# UWB-Anchor_Sch.net
KiCad netlist of a schematic drawn in Altium Designer
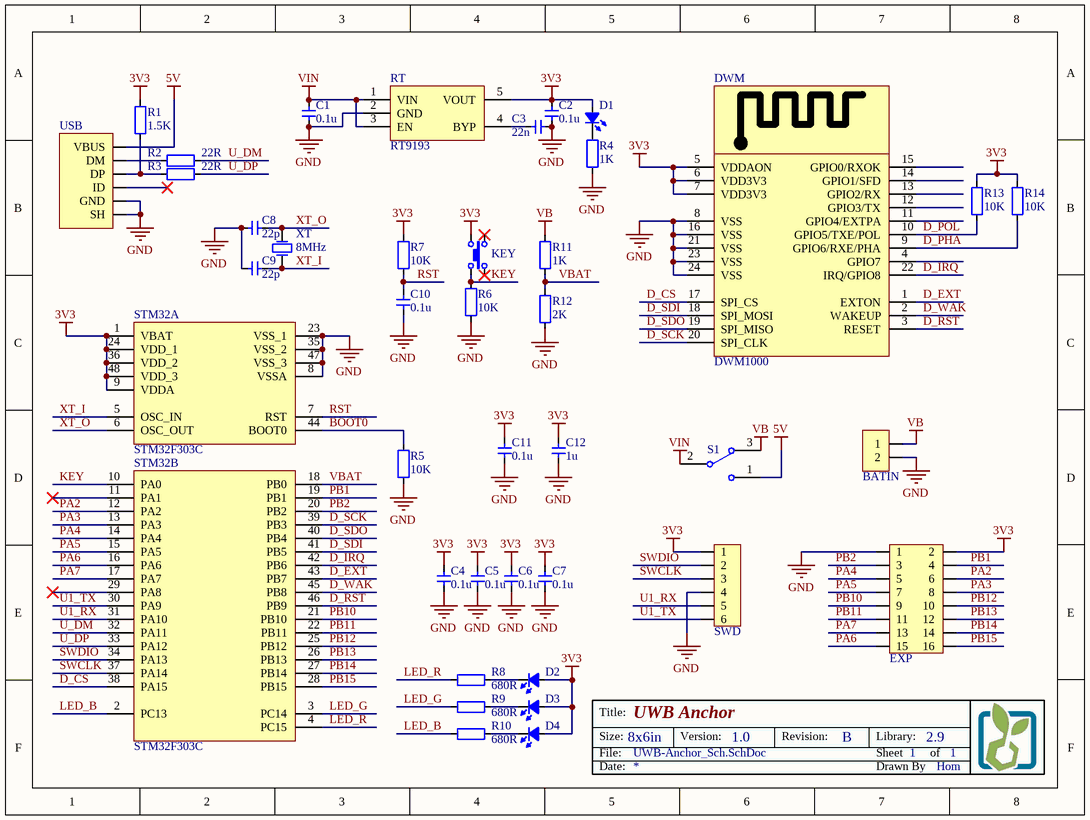
[diagram p0: UWB-Anchor_Sch.SchDoc]

(export (version "E")
  (design (tool "Eeschema 10.0.6"))
  (components
    (comp (ref "BATIN")
      (value "MX1.25_2P")
      (footprint "PCB_Connector:MX1.25_S90_2P")
      (description "MX")
      (libsource (lib "SCH_Connector") (part "MX1.25_2P"))
    )
    (comp (ref "C1")
      (value "0.1u")
      (footprint "PCB_PassiveCap:CAP_0603")
      (description "Capacitor")
      (fields (field (name "Comment") "Cap_0603"))
      (libsource (lib "SCH_Passive") (part "Cap_0603"))
    )
    (comp (ref "C2")
      (value "0.1u")
      (footprint "PCB_PassiveCap:CAP_0603")
      (description "Capacitor")
      (fields (field (name "Comment") "Cap_0603"))
      (libsource (lib "SCH_Passive") (part "Cap_0603"))
    )
    (comp (ref "C3")
      (value "22n")
      (footprint "PCB_PassiveCap:CAP_0603")
      (description "Capacitor")
      (fields (field (name "Comment") "Cap_0603"))
      (libsource (lib "SCH_Passive") (part "Cap_0603"))
    )
    (comp (ref "C4")
      (value "0.1u")
      (footprint "PCB_PassiveCap:CAP_0603")
      (description "Capacitor")
      (fields (field (name "Comment") "Cap_0603"))
      (libsource (lib "SCH_Passive") (part "Cap_0603"))
    )
    (comp (ref "C5")
      (value "0.1u")
      (footprint "PCB_PassiveCap:CAP_0603")
      (description "Capacitor")
      (fields (field (name "Comment") "Cap_0603"))
      (libsource (lib "SCH_Passive") (part "Cap_0603"))
    )
    (comp (ref "C6")
      (value "0.1u")
      (footprint "PCB_PassiveCap:CAP_0603")
      (description "Capacitor")
      (fields (field (name "Comment") "Cap_0603"))
      (libsource (lib "SCH_Passive") (part "Cap_0603"))
    )
    (comp (ref "C7")
      (value "0.1u")
      (footprint "PCB_PassiveCap:CAP_0603")
      (description "Capacitor")
      (fields (field (name "Comment") "Cap_0603"))
      (libsource (lib "SCH_Passive") (part "Cap_0603"))
    )
    (comp (ref "C8")
      (value "22p")
      (footprint "PCB_PassiveCap:CAP_0603")
      (description "Capacitor")
      (fields (field (name "Comment") "Cap_0603"))
      (libsource (lib "SCH_Passive") (part "Cap_0603"))
    )
    (comp (ref "C9")
      (value "22p")
      (footprint "PCB_PassiveCap:CAP_0603")
      (description "Capacitor")
      (fields (field (name "Comment") "Cap_0603"))
      (libsource (lib "SCH_Passive") (part "Cap_0603"))
    )
    (comp (ref "C10")
      (value "0.1u")
      (footprint "PCB_PassiveCap:CAP_0603")
      (description "Capacitor")
      (fields (field (name "Comment") "Cap_0603"))
      (libsource (lib "SCH_Passive") (part "Cap_0603"))
    )
    (comp (ref "C11")
      (value "0.1u")
      (footprint "PCB_PassiveCap:CAP_0603")
      (description "Capacitor")
      (fields (field (name "Comment") "Cap_0603"))
      (libsource (lib "SCH_Passive") (part "Cap_0603"))
    )
    (comp (ref "C12")
      (value "1u")
      (footprint "PCB_PassiveCap:CAP_0603")
      (description "Capacitor")
      (fields (field (name "Comment") "Cap_0603"))
      (libsource (lib "SCH_Passive") (part "Cap_0603"))
    )
    (comp (ref "D1")
      (value "LED_0603")
      (footprint "PCB_ActiveLED:LED_0603_YELLOW")
      (description "LED")
      (libsource (lib "SCH_Active") (part "LED_0603"))
    )
    (comp (ref "D2")
      (value "LED_0603")
      (footprint "PCB_ActiveLED:LED_0603_RED")
      (description "LED")
      (libsource (lib "SCH_Active") (part "LED_0603"))
    )
    (comp (ref "D3")
      (value "LED_0603")
      (footprint "PCB_ActiveLED:LED_0603_GREEN")
      (description "LED")
      (libsource (lib "SCH_Active") (part "LED_0603"))
    )
    (comp (ref "D4")
      (value "LED_0603")
      (footprint "PCB_ActiveLED:LED_0603_BLUE")
      (description "LED")
      (libsource (lib "SCH_Active") (part "LED_0603"))
    )
    (comp (ref "DWM")
      (value "DWM1000")
      (footprint "PCB_Module:DWM1000")
      (description "Module")
      (fields (field (name "MANUFACTURER") "Decawave Limited"))
      (libsource (lib "SCH_Module") (part "DWM1000"))
    )
    (comp (ref "EXP")
      (value "HDR2x8_2.54")
      (footprint "PCB_ConnectorHDR:HDR2X8_2.54_180")
      (description "Header")
      (libsource (lib "SCH_ConnectorHDR") (part "HDR2x8_2.54"))
    )
    (comp (ref "KEY")
      (value "ButtonTACT")
      (footprint "PCB_Switch:ButtonTACT_3.5*3.55_90")
      (description "Button")
      (libsource (lib "SCH_Switch") (part "ButtonTACT"))
    )
    (comp (ref "R1")
      (value "1.5K")
      (footprint "PCB_PassiveRes:RES_0603")
      (description "Resistor")
      (fields (field (name "Comment") "Res_0603"))
      (libsource (lib "") (part "Res_0603_1"))
    )
    (comp (ref "R2")
      (value "22R")
      (footprint "PCB_PassiveRes:RES_0603")
      (description "Resistor")
      (fields (field (name "Comment") "Res_0603"))
      (libsource (lib "") (part "Res_0603_3"))
    )
    (comp (ref "R3")
      (value "22R")
      (footprint "PCB_PassiveRes:RES_0603")
      (description "Resistor")
      (fields (field (name "Comment") "Res_0603"))
      (libsource (lib "") (part "Res_0603_3"))
    )
    (comp (ref "R4")
      (value "1K")
      (footprint "PCB_PassiveRes:RES_0603")
      (description "Resistor")
      (fields (field (name "Comment") "Res_0603"))
      (libsource (lib "") (part "Res_0603_2"))
    )
    (comp (ref "R5")
      (value "10K")
      (footprint "PCB_PassiveRes:RES_0603")
      (description "Resistor")
      (fields (field (name "Comment") "Res_0603"))
      (libsource (lib "") (part "Res_0603_2"))
    )
    (comp (ref "R6")
      (value "10K")
      (footprint "PCB_PassiveRes:RES_0603")
      (description "Resistor")
      (fields (field (name "Comment") "Res_0603"))
      (libsource (lib "") (part "Res_0603_2"))
    )
    (comp (ref "R7")
      (value "10K")
      (footprint "PCB_PassiveRes:RES_0603")
      (description "Resistor")
      (fields (field (name "Comment") "Res_0603"))
      (libsource (lib "") (part "Res_0603_2"))
    )
    (comp (ref "R8")
      (value "680R")
      (footprint "PCB_PassiveRes:RES_0603")
      (description "Resistor")
      (fields (field (name "Comment") "Res_0603"))
      (libsource (lib "SCH_Passive") (part "Res_0603"))
    )
    (comp (ref "R9")
      (value "680R")
      (footprint "PCB_PassiveRes:RES_0603")
      (description "Resistor")
      (fields (field (name "Comment") "Res_0603"))
      (libsource (lib "SCH_Passive") (part "Res_0603"))
    )
    (comp (ref "R10")
      (value "680R")
      (footprint "PCB_PassiveRes:RES_0603")
      (description "Resistor")
      (fields (field (name "Comment") "Res_0603"))
      (libsource (lib "SCH_Passive") (part "Res_0603"))
    )
    (comp (ref "R11")
      (value "1K")
      (footprint "PCB_PassiveRes:RES_0603")
      (description "Resistor")
      (fields (field (name "Comment") "Res_0603"))
      (libsource (lib "") (part "Res_0603_1"))
    )
    (comp (ref "R12")
      (value "2K")
      (footprint "PCB_PassiveRes:RES_0603")
      (description "Resistor")
      (fields (field (name "Comment") "Res_0603"))
      (libsource (lib "") (part "Res_0603_1"))
    )
    (comp (ref "R13")
      (value "10K")
      (footprint "PCB_PassiveRes:RES_0603")
      (description "Resistor")
      (fields (field (name "Comment") "Res_0603"))
      (libsource (lib "") (part "Res_0603_2"))
    )
    (comp (ref "R14")
      (value "10K")
      (footprint "PCB_PassiveRes:RES_0603")
      (description "Resistor")
      (fields (field (name "Comment") "Res_0603"))
      (libsource (lib "") (part "Res_0603_2"))
    )
    (comp (ref "RT")
      (value "RT9193")
      (footprint "PCB_IntegratedCircuit:SOT23-5")
      (description "Power")
      (libsource (lib "SCH_IntegratedCircuit") (part "RT9193"))
    )
    (comp (ref "S1")
      (value "SwitchSPDT_2.8x6.6_90")
      (footprint "PCB_Switch:SwitchSPDT_2.8X6.6_90")
      (description "Switch")
      (libsource (lib "SCH_Switch") (part "SwitchSPDT_2.8x6.6_90"))
    )
    (comp (ref "STM32")
      (value "STM32F303C")
      (footprint "PCB_IntegratedCircuit:LQFP_P0.5_48")
      (description "MCU")
      (libsource (lib "SCH_IntegratedCircuit") (part "STM32F103C"))
    )
    (comp (ref "SWD")
      (value "HDR1x6_1.27")
      (footprint "PCB_ConnectorHDR:HDR1X6_1.27_180HFD")
      (description "Header")
      (libsource (lib "SCH_ConnectorHDR") (part "HDR1x6_1.27"))
    )
    (comp (ref "USB")
      (value "USB_Micro")
      (footprint "PCB_USB:USB_Micro-AB")
      (description "USB")
      (libsource (lib "SCH_USB") (part "USB_Micro"))
    )
    (comp (ref "XT")
      (value "8MHz")
      (footprint "PCB_Oscillator:XT_5032_2")
      (description "Crystal Oscillator")
      (fields (field (name "Comment") "XTAL_5032_2P"))
      (libsource (lib "SCH_Oscillator") (part "XTAL_5032_2P"))
    )
  )
  (nets
    (net (code "1") (name "/BOOT0") (class "Default")
      (node (ref "R5") (pin "2") (pinfunction "2_2") (pintype "passive"))
      (node (ref "STM32") (pin "44") (pinfunction "BOOT0_44") (pintype "passive"))
    )
    (net (code "2") (name "/D_CS") (class "Default")
      (node (ref "DWM") (pin "17") (pinfunction "SPI_CS_17") (pintype "passive"))
      (node (ref "STM32") (pin "38") (pinfunction "PA15_38") (pintype "passive"))
    )
    (net (code "3") (name "/D_EXT") (class "Default")
      (node (ref "DWM") (pin "1") (pinfunction "EXTON_1") (pintype "passive"))
      (node (ref "STM32") (pin "43") (pinfunction "PB7_43") (pintype "passive"))
    )
    (net (code "4") (name "/D_IRQ") (class "Default")
      (node (ref "DWM") (pin "22") (pinfunction "IRQ/GPIO8_22") (pintype "passive"))
      (node (ref "STM32") (pin "42") (pinfunction "PB6_42") (pintype "passive"))
    )
    (net (code "5") (name "/D_PHA") (class "Default")
      (node (ref "DWM") (pin "9") (pinfunction "GPIO6/RXE/PHA_9") (pintype "passive"))
      (node (ref "R14") (pin "1") (pinfunction "1_1") (pintype "passive"))
    )
    (net (code "6") (name "/D_POL") (class "Default")
      (node (ref "DWM") (pin "10") (pinfunction "GPIO5/TXE/POL_10") (pintype "passive"))
      (node (ref "R13") (pin "1") (pinfunction "1_1") (pintype "passive"))
    )
    (net (code "7") (name "/D_RST") (class "Default")
      (node (ref "DWM") (pin "3") (pinfunction "RESET_3") (pintype "passive"))
      (node (ref "STM32") (pin "46") (pinfunction "PB9_46") (pintype "passive"))
    )
    (net (code "8") (name "/D_SCK") (class "Default")
      (node (ref "DWM") (pin "20") (pinfunction "SPI_CLK_20") (pintype "passive"))
      (node (ref "STM32") (pin "39") (pinfunction "PB3_39") (pintype "passive"))
    )
    (net (code "9") (name "/D_SDI") (class "Default")
      (node (ref "DWM") (pin "18") (pinfunction "SPI_MOSI_18") (pintype "passive"))
      (node (ref "STM32") (pin "41") (pinfunction "PB5_41") (pintype "passive"))
    )
    (net (code "10") (name "/D_SDO") (class "Default")
      (node (ref "DWM") (pin "19") (pinfunction "SPI_MISO_19") (pintype "passive"))
      (node (ref "STM32") (pin "40") (pinfunction "PB4_40") (pintype "passive"))
    )
    (net (code "11") (name "/D_WAK") (class "Default")
      (node (ref "DWM") (pin "2") (pinfunction "WAKEUP_2") (pintype "passive"))
      (node (ref "STM32") (pin "45") (pinfunction "PB8_45") (pintype "passive"))
    )
    (net (code "12") (name "/KEY") (class "Default")
      (node (ref "KEY") (pin "1") (pinfunction "1_1") (pintype "passive"))
      (node (ref "R6") (pin "2") (pinfunction "2_2") (pintype "passive"))
      (node (ref "STM32") (pin "10") (pinfunction "PA0_10") (pintype "passive"))
    )
    (net (code "13") (name "/LED_B") (class "Default")
      (node (ref "R10") (pin "2") (pinfunction "2_2") (pintype "passive"))
      (node (ref "STM32") (pin "2") (pinfunction "PC13_2") (pintype "passive"))
    )
    (net (code "14") (name "/LED_G") (class "Default")
      (node (ref "R9") (pin "2") (pinfunction "2_2") (pintype "passive"))
      (node (ref "STM32") (pin "3") (pinfunction "PC14_3") (pintype "passive"))
    )
    (net (code "15") (name "/LED_R") (class "Default")
      (node (ref "R8") (pin "2") (pinfunction "2_2") (pintype "passive"))
      (node (ref "STM32") (pin "4") (pinfunction "PC15_4") (pintype "passive"))
    )
    (net (code "16") (name "/PA2") (class "Default")
      (node (ref "EXP") (pin "6") (pinfunction "6_6") (pintype "passive"))
      (node (ref "STM32") (pin "12") (pinfunction "PA2_12") (pintype "passive"))
    )
    (net (code "17") (name "/PA3") (class "Default")
      (node (ref "EXP") (pin "8") (pinfunction "8_8") (pintype "passive"))
      (node (ref "STM32") (pin "13") (pinfunction "PA3_13") (pintype "passive"))
    )
    (net (code "18") (name "/PA4") (class "Default")
      (node (ref "EXP") (pin "5") (pinfunction "5_5") (pintype "passive"))
      (node (ref "STM32") (pin "14") (pinfunction "PA4_14") (pintype "passive"))
    )
    (net (code "19") (name "/PA5") (class "Default")
      (node (ref "EXP") (pin "7") (pinfunction "7_7") (pintype "passive"))
      (node (ref "STM32") (pin "15") (pinfunction "PA5_15") (pintype "passive"))
    )
    (net (code "20") (name "/PA6") (class "Default")
      (node (ref "EXP") (pin "15") (pinfunction "15_15") (pintype "passive"))
      (node (ref "STM32") (pin "16") (pinfunction "PA6_16") (pintype "passive"))
    )
    (net (code "21") (name "/PA7") (class "Default")
      (node (ref "EXP") (pin "13") (pinfunction "13_13") (pintype "passive"))
      (node (ref "STM32") (pin "17") (pinfunction "PA7_17") (pintype "passive"))
    )
    (net (code "22") (name "/PB1") (class "Default")
      (node (ref "EXP") (pin "4") (pinfunction "4_4") (pintype "passive"))
      (node (ref "STM32") (pin "19") (pinfunction "PB1_19") (pintype "passive"))
    )
    (net (code "23") (name "/PB2") (class "Default")
      (node (ref "EXP") (pin "3") (pinfunction "3_3") (pintype "passive"))
      (node (ref "STM32") (pin "20") (pinfunction "PB2_20") (pintype "passive"))
    )
    (net (code "24") (name "/PB10") (class "Default")
      (node (ref "EXP") (pin "9") (pinfunction "9_9") (pintype "passive"))
      (node (ref "STM32") (pin "21") (pinfunction "PB10_21") (pintype "passive"))
    )
    (net (code "25") (name "/PB11") (class "Default")
      (node (ref "EXP") (pin "11") (pinfunction "11_11") (pintype "passive"))
      (node (ref "STM32") (pin "22") (pinfunction "PB11_22") (pintype "passive"))
    )
    (net (code "26") (name "/PB12") (class "Default")
      (node (ref "EXP") (pin "10") (pinfunction "10_10") (pintype "passive"))
      (node (ref "STM32") (pin "25") (pinfunction "PB12_25") (pintype "passive"))
    )
    (net (code "27") (name "/PB13") (class "Default")
      (node (ref "EXP") (pin "12") (pinfunction "12_12") (pintype "passive"))
      (node (ref "STM32") (pin "26") (pinfunction "PB13_26") (pintype "passive"))
    )
    (net (code "28") (name "/PB14") (class "Default")
      (node (ref "EXP") (pin "14") (pinfunction "14_14") (pintype "passive"))
      (node (ref "STM32") (pin "27") (pinfunction "PB14_27") (pintype "passive"))
    )
    (net (code "29") (name "/PB15") (class "Default")
      (node (ref "EXP") (pin "16") (pinfunction "16_16") (pintype "passive"))
      (node (ref "STM32") (pin "28") (pinfunction "PB15_28") (pintype "passive"))
    )
    (net (code "30") (name "/RST") (class "Default")
      (node (ref "C10") (pin "2") (pinfunction "2_2") (pintype "passive"))
      (node (ref "R7") (pin "1") (pinfunction "1_1") (pintype "passive"))
      (node (ref "STM32") (pin "7") (pinfunction "RST_7") (pintype "passive"))
    )
    (net (code "31") (name "/SWCLK") (class "Default")
      (node (ref "STM32") (pin "37") (pinfunction "PA14_37") (pintype "passive"))
      (node (ref "SWD") (pin "3") (pinfunction "3_3") (pintype "passive"))
    )
    (net (code "32") (name "/SWDIO") (class "Default")
      (node (ref "STM32") (pin "34") (pinfunction "PA13_34") (pintype "passive"))
      (node (ref "SWD") (pin "2") (pinfunction "2_2") (pintype "passive"))
    )
    (net (code "33") (name "/U1_RX") (class "Default")
      (node (ref "STM32") (pin "31") (pinfunction "PA10_31") (pintype "passive"))
      (node (ref "SWD") (pin "5") (pinfunction "5_5") (pintype "passive"))
    )
    (net (code "34") (name "/U1_TX") (class "Default")
      (node (ref "STM32") (pin "30") (pinfunction "PA9_30") (pintype "passive"))
      (node (ref "SWD") (pin "6") (pinfunction "6_6") (pintype "passive"))
    )
    (net (code "35") (name "/U_DM") (class "Default")
      (node (ref "R2") (pin "2") (pinfunction "2_2") (pintype "passive"))
      (node (ref "STM32") (pin "32") (pinfunction "PA11_32") (pintype "passive"))
    )
    (net (code "36") (name "/U_DP") (class "Default")
      (node (ref "R3") (pin "2") (pinfunction "2_2") (pintype "passive"))
      (node (ref "STM32") (pin "33") (pinfunction "PA12_33") (pintype "passive"))
    )
    (net (code "37") (name "/VBAT") (class "Default")
      (node (ref "R11") (pin "2") (pinfunction "2_2") (pintype "passive"))
      (node (ref "R12") (pin "1") (pinfunction "1_1") (pintype "passive"))
      (node (ref "STM32") (pin "18") (pinfunction "PB0_18") (pintype "passive"))
    )
    (net (code "38") (name "/XT_I") (class "Default")
      (node (ref "C9") (pin "1") (pinfunction "1_1") (pintype "passive"))
      (node (ref "STM32") (pin "5") (pinfunction "OSC_IN_5") (pintype "passive"))
      (node (ref "XT") (pin "1") (pinfunction "OSC1_1") (pintype "passive"))
    )
    (net (code "39") (name "/XT_O") (class "Default")
      (node (ref "C8") (pin "1") (pinfunction "1_1") (pintype "passive"))
      (node (ref "STM32") (pin "6") (pinfunction "OSC_OUT_6") (pintype "passive"))
      (node (ref "XT") (pin "2") (pinfunction "OSC2_2") (pintype "passive"))
    )
    (net (code "40") (name "3V3") (class "Default")
      (node (ref "C11") (pin "1") (pinfunction "1_1") (pintype "passive"))
      (node (ref "C12") (pin "1") (pinfunction "1_1") (pintype "passive"))
      (node (ref "C2") (pin "2") (pinfunction "2_2") (pintype "passive"))
      (node (ref "C4") (pin "2") (pinfunction "2_2") (pintype "passive"))
      (node (ref "C5") (pin "2") (pinfunction "2_2") (pintype "passive"))
      (node (ref "C6") (pin "2") (pinfunction "2_2") (pintype "passive"))
      (node (ref "C7") (pin "2") (pinfunction "2_2") (pintype "passive"))
      (node (ref "D1") (pin "1") (pinfunction "A_1") (pintype "passive"))
      (node (ref "D2") (pin "1") (pinfunction "A_1") (pintype "passive"))
      (node (ref "D3") (pin "1") (pinfunction "A_1") (pintype "passive"))
      (node (ref "D4") (pin "1") (pinfunction "A_1") (pintype "passive"))
      (node (ref "DWM") (pin "5") (pinfunction "VDDAON_5") (pintype "passive"))
      (node (ref "DWM") (pin "6") (pinfunction "VDD3V3_6") (pintype "passive"))
      (node (ref "DWM") (pin "7") (pinfunction "VDD3V3_7") (pintype "passive"))
      (node (ref "EXP") (pin "2") (pinfunction "2_2") (pintype "passive"))
      (node (ref "KEY") (pin "2") (pinfunction "2_2") (pintype "passive"))
      (node (ref "R1") (pin "1") (pinfunction "1_1") (pintype "passive"))
      (node (ref "R13") (pin "2") (pinfunction "2_2") (pintype "passive"))
      (node (ref "R14") (pin "2") (pinfunction "2_2") (pintype "passive"))
      (node (ref "R7") (pin "2") (pinfunction "2_2") (pintype "passive"))
      (node (ref "RT") (pin "5") (pinfunction "VOUT_5") (pintype "passive"))
      (node (ref "STM32") (pin "1") (pinfunction "VBAT_1") (pintype "passive"))
      (node (ref "STM32") (pin "24") (pinfunction "VDD_1_24") (pintype "passive"))
      (node (ref "STM32") (pin "36") (pinfunction "VDD_2_36") (pintype "passive"))
      (node (ref "STM32") (pin "48") (pinfunction "VDD_3_48") (pintype "passive"))
      (node (ref "STM32") (pin "9") (pinfunction "VDDA_9") (pintype "passive"))
      (node (ref "SWD") (pin "1") (pinfunction "1_1") (pintype "passive"))
    )
    (net (code "41") (name "5V") (class "Default")
      (node (ref "S1") (pin "1") (pinfunction "1_1") (pintype "passive"))
      (node (ref "USB") (pin "1") (pinfunction "VBUS_1") (pintype "passive"))
    )
    (net (code "42") (name "GND") (class "Default")
      (node (ref "BATIN") (pin "2") (pinfunction "2_2") (pintype "passive"))
      (node (ref "C1") (pin "1") (pinfunction "1_1") (pintype "passive"))
      (node (ref "C10") (pin "1") (pinfunction "1_1") (pintype "passive"))
      (node (ref "C11") (pin "2") (pinfunction "2_2") (pintype "passive"))
      (node (ref "C12") (pin "2") (pinfunction "2_2") (pintype "passive"))
      (node (ref "C2") (pin "1") (pinfunction "1_1") (pintype "passive"))
      (node (ref "C3") (pin "1") (pinfunction "1_1") (pintype "passive"))
      (node (ref "C4") (pin "1") (pinfunction "1_1") (pintype "passive"))
      (node (ref "C5") (pin "1") (pinfunction "1_1") (pintype "passive"))
      (node (ref "C6") (pin "1") (pinfunction "1_1") (pintype "passive"))
      (node (ref "C7") (pin "1") (pinfunction "1_1") (pintype "passive"))
      (node (ref "C8") (pin "2") (pinfunction "2_2") (pintype "passive"))
      (node (ref "C9") (pin "2") (pinfunction "2_2") (pintype "passive"))
      (node (ref "DWM") (pin "16") (pinfunction "VSS_16") (pintype "passive"))
      (node (ref "DWM") (pin "21") (pinfunction "VSS_21") (pintype "passive"))
      (node (ref "DWM") (pin "23") (pinfunction "VSS_23") (pintype "passive"))
      (node (ref "DWM") (pin "24") (pinfunction "VSS_24") (pintype "passive"))
      (node (ref "DWM") (pin "8") (pinfunction "VSS_8") (pintype "passive"))
      (node (ref "EXP") (pin "1") (pinfunction "1_1") (pintype "passive"))
      (node (ref "R12") (pin "2") (pinfunction "2_2") (pintype "passive"))
      (node (ref "R4") (pin "1") (pinfunction "1_1") (pintype "passive"))
      (node (ref "R5") (pin "1") (pinfunction "1_1") (pintype "passive"))
      (node (ref "R6") (pin "1") (pinfunction "1_1") (pintype "passive"))
      (node (ref "RT") (pin "2") (pinfunction "GND_2") (pintype "passive"))
      (node (ref "STM32") (pin "23") (pinfunction "VSS_1_23") (pintype "passive"))
      (node (ref "STM32") (pin "35") (pinfunction "VSS_2_35") (pintype "passive"))
      (node (ref "STM32") (pin "47") (pinfunction "VSS_3_47") (pintype "passive"))
      (node (ref "STM32") (pin "8") (pinfunction "VSSA_8") (pintype "passive"))
      (node (ref "SWD") (pin "4") (pinfunction "4_4") (pintype "passive"))
      (node (ref "USB") (pin "0") (pinfunction "SH_0") (pintype "passive"))
      (node (ref "USB") (pin "5") (pinfunction "GND_5") (pintype "passive"))
    )
    (net (code "43") (name "Net-(D1-K)") (class "Default")
      (node (ref "D1") (pin "2") (pinfunction "K_2") (pintype "passive"))
      (node (ref "R4") (pin "2") (pinfunction "2_2") (pintype "passive"))
    )
    (net (code "44") (name "Net-(D2-K)") (class "Default")
      (node (ref "D2") (pin "2") (pinfunction "K_2") (pintype "passive"))
      (node (ref "R8") (pin "1") (pinfunction "1_1") (pintype "passive"))
    )
    (net (code "45") (name "Net-(D3-K)") (class "Default")
      (node (ref "D3") (pin "2") (pinfunction "K_2") (pintype "passive"))
      (node (ref "R9") (pin "1") (pinfunction "1_1") (pintype "passive"))
    )
    (net (code "46") (name "Net-(D4-K)") (class "Default")
      (node (ref "D4") (pin "2") (pinfunction "K_2") (pintype "passive"))
      (node (ref "R10") (pin "1") (pinfunction "1_1") (pintype "passive"))
    )
    (net (code "47") (name "Net-(RT-BYP)") (class "Default")
      (node (ref "C3") (pin "2") (pinfunction "2_2") (pintype "passive"))
      (node (ref "RT") (pin "4") (pinfunction "BYP_4") (pintype "passive"))
    )
    (net (code "48") (name "Net-(USB-DM)") (class "Default")
      (node (ref "R2") (pin "1") (pinfunction "1_1") (pintype "passive"))
      (node (ref "USB") (pin "2") (pinfunction "DM_2") (pintype "passive"))
    )
    (net (code "49") (name "Net-(USB-DP)") (class "Default")
      (node (ref "R1") (pin "2") (pinfunction "2_2") (pintype "passive"))
      (node (ref "R3") (pin "1") (pinfunction "1_1") (pintype "passive"))
      (node (ref "USB") (pin "3") (pinfunction "DP_3") (pintype "passive"))
    )
    (net (code "50") (name "VB") (class "Default")
      (node (ref "BATIN") (pin "1") (pinfunction "1_1") (pintype "passive"))
      (node (ref "R11") (pin "1") (pinfunction "1_1") (pintype "passive"))
      (node (ref "S1") (pin "3") (pinfunction "3_3") (pintype "passive"))
    )
    (net (code "51") (name "VIN") (class "Default")
      (node (ref "C1") (pin "2") (pinfunction "2_2") (pintype "passive"))
      (node (ref "RT") (pin "1") (pinfunction "VIN_1") (pintype "passive"))
      (node (ref "RT") (pin "3") (pinfunction "EN_3") (pintype "power_in"))
      (node (ref "S1") (pin "2") (pinfunction "2_2") (pintype "passive"))
    )
    (net (code "52") (name "unconnected-(DWM-GPIO0{slash}RXOK-Pad15)") (class "Default")
      (node (ref "DWM") (pin "15") (pinfunction "GPIO0/RXOK_15") (pintype "passive"))
    )
    (net (code "53") (name "unconnected-(DWM-GPIO1{slash}SFD-Pad14)") (class "Default")
      (node (ref "DWM") (pin "14") (pinfunction "GPIO1/SFD_14") (pintype "passive"))
    )
    (net (code "54") (name "unconnected-(DWM-GPIO2{slash}RX-Pad13)") (class "Default")
      (node (ref "DWM") (pin "13") (pinfunction "GPIO2/RX_13") (pintype "passive"))
    )
    (net (code "55") (name "unconnected-(DWM-GPIO3{slash}TX-Pad12)") (class "Default")
      (node (ref "DWM") (pin "12") (pinfunction "GPIO3/TX_12") (pintype "passive"))
    )
    (net (code "56") (name "unconnected-(DWM-GPIO4{slash}EXTPA-Pad11)") (class "Default")
      (node (ref "DWM") (pin "11") (pinfunction "GPIO4/EXTPA_11") (pintype "passive"))
    )
    (net (code "57") (name "unconnected-(DWM-GPIO7-Pad4)") (class "Default")
      (node (ref "DWM") (pin "4") (pinfunction "GPIO7_4") (pintype "passive"))
    )
    (net (code "58") (name "unconnected-(KEY-Pad3)") (class "Default")
      (node (ref "KEY") (pin "3") (pinfunction "3_3") (pintype "passive+no_connect"))
    )
    (net (code "59") (name "unconnected-(KEY-Pad4)") (class "Default")
      (node (ref "KEY") (pin "4") (pinfunction "4_4") (pintype "passive+no_connect"))
    )
    (net (code "60") (name "unconnected-(STM32B-PA1-Pad11)") (class "Default")
      (node (ref "STM32") (pin "11") (pinfunction "PA1_11") (pintype "passive+no_connect"))
    )
    (net (code "61") (name "unconnected-(STM32B-PA8-Pad29)") (class "Default")
      (node (ref "STM32") (pin "29") (pinfunction "PA8_29") (pintype "passive+no_connect"))
    )
    (net (code "62") (name "unconnected-(USB-ID-Pad4)") (class "Default")
      (node (ref "USB") (pin "4") (pinfunction "ID_4") (pintype "passive+no_connect"))
    )
  )
)
